# HomeAutomationModule.net
KiCad netlist of a schematic drawn in EAGLE
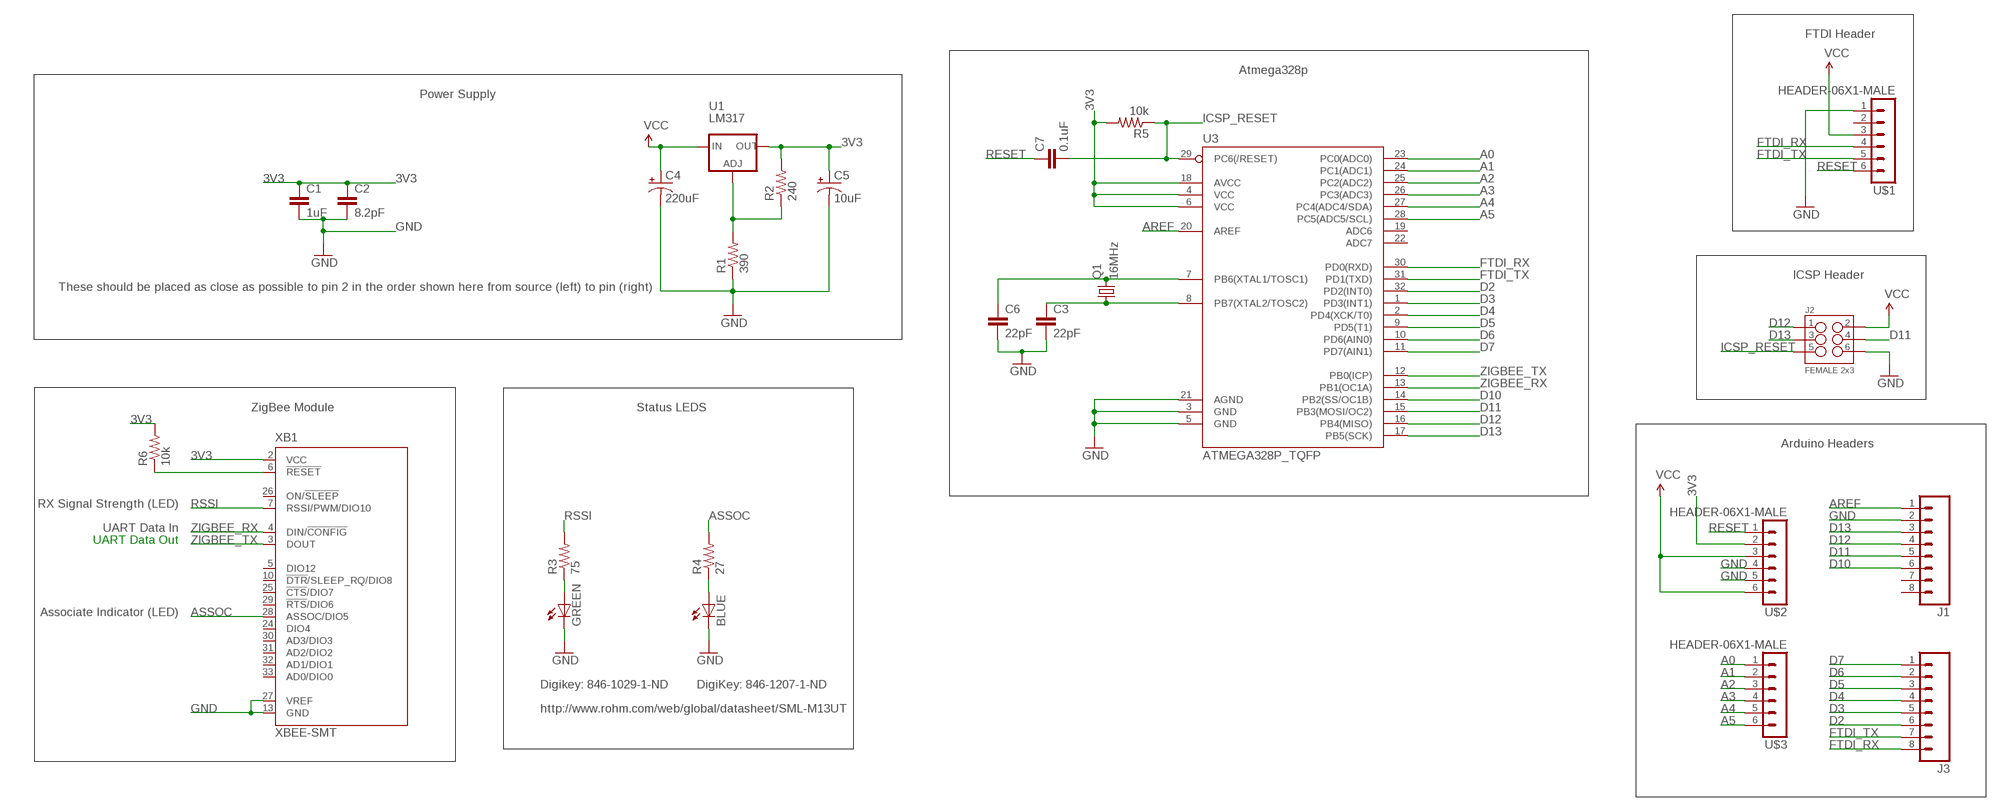
[diagram p0: schematic, sheet 1]

(export (version "E")
  (design (tool "Eeschema 10.0.6"))
  (components
    (comp (ref "BLUE")
      (value "LEDCHIP-LED0805")
      (footprint "eagle-import:CHIP-LED0805")
      (libsource (lib "eagle-import") (part "LEDCHIP-LED0805"))
    )
    (comp (ref "C1")
      (value "1uF")
      (footprint "eagle-import:0805-CAP")
      (libsource (lib "eagle-import") (part "1.0UF-25V-+80/-20(0805){dblquote}"))
    )
    (comp (ref "C2")
      (value "8.2pF")
      (footprint "eagle-import:0805-CAP")
      (libsource (lib "eagle-import") (part "1.0UF-25V-+80/-20(0805){dblquote}"))
    )
    (comp (ref "C3")
      (value "22pF")
      (footprint "eagle-import:0805-CAP")
      (libsource (lib "eagle-import") (part "2.2UF-25V-+80/-20(0805)"))
    )
    (comp (ref "C4")
      (value "220uF")
      (footprint "eagle-import:CPOL-RADIAL-10UF-25V")
      (libsource (lib "eagle-import") (part "CAP_POLPTH2"))
    )
    (comp (ref "C5")
      (value "10uF")
      (footprint "eagle-import:CPOL-RADIAL-10UF-25V")
      (libsource (lib "eagle-import") (part "CAP_POLPTH2"))
    )
    (comp (ref "C6")
      (value "22pF")
      (footprint "eagle-import:0805-CAP")
      (libsource (lib "eagle-import") (part "2.2UF-25V-+80/-20(0805)"))
    )
    (comp (ref "C7")
      (value "0.1uF")
      (footprint "eagle-import:0805-CAP")
      (libsource (lib "eagle-import") (part "2.2UF-25V-+80/-20(0805)"))
    )
    (comp (ref "GREEN")
      (value "LEDCHIP-LED0805")
      (footprint "eagle-import:CHIP-LED0805")
      (libsource (lib "eagle-import") (part "LEDCHIP-LED0805"))
    )
    (comp (ref "J1")
      (value "M08")
      (footprint "eagle-import:1X08_ROUND")
      (libsource (lib "eagle-import") (part "M08"))
    )
    (comp (ref "J2")
      (value "FEMALE 2x3")
      (footprint "eagle-import:2X3")
      (libsource (lib "eagle-import") (part "M03X2FEMALE"))
    )
    (comp (ref "J3")
      (value "M08")
      (footprint "eagle-import:1X08_ROUND")
      (libsource (lib "eagle-import") (part "M08"))
    )
    (comp (ref "Q1")
      (value "16MHz")
      (footprint "eagle-import:HC49_S")
      (libsource (lib "eagle-import") (part "CRYSTALHC49S"))
    )
    (comp (ref "R1")
      (value "390")
      (footprint "eagle-import:0805")
      (libsource (lib "eagle-import") (part "RESISTOR0805-RES"))
    )
    (comp (ref "R2")
      (value "240")
      (footprint "eagle-import:0805")
      (libsource (lib "eagle-import") (part "RESISTOR0805-RES"))
    )
    (comp (ref "R3")
      (value "75")
      (footprint "eagle-import:0805")
      (libsource (lib "eagle-import") (part "RESISTOR0805-RES"))
    )
    (comp (ref "R4")
      (value "27")
      (footprint "eagle-import:0805")
      (libsource (lib "eagle-import") (part "RESISTOR0805-RES"))
    )
    (comp (ref "R5")
      (value "10k")
      (footprint "eagle-import:0805")
      (libsource (lib "eagle-import") (part "RESISTOR0805-RES"))
    )
    (comp (ref "R6")
      (value "10k")
      (footprint "eagle-import:0805")
      (libsource (lib "eagle-import") (part "RESISTOR0805-RES"))
    )
    (comp (ref "U$1")
      (value "HEADER-06X1-MALE")
      (footprint "eagle-import:06X1-PTH")
      (libsource (lib "eagle-import") (part "HEADER-06X1?-MALE"))
    )
    (comp (ref "U$2")
      (value "HEADER-06X1-MALE")
      (footprint "eagle-import:06X1-PTH")
      (libsource (lib "eagle-import") (part "HEADER-06X1?-MALE"))
    )
    (comp (ref "U$3")
      (value "HEADER-06X1-MALE")
      (footprint "eagle-import:06X1-PTH")
      (libsource (lib "eagle-import") (part "HEADER-06X1?-MALE"))
    )
    (comp (ref "U1")
      (value "LM317")
      (footprint "eagle-import:SOT223")
      (libsource (lib "eagle-import") (part "V_REG_317SMD"))
    )
    (comp (ref "U3")
      (value "ATMEGA328P_TQFP")
      (footprint "eagle-import:TQFP32-08")
      (libsource (lib "eagle-import") (part "ATMEGA328P_TQFP"))
    )
    (comp (ref "XB1")
      (value "XBEE-SMT")
      (footprint "eagle-import:XBEE-SMT")
      (libsource (lib "eagle-import") (part "XBEE-SMT"))
    )
  )
  (nets
    (net (code "1") (name "/3V3") (class "Default")
      (node (ref "C1") (pin "1") (pinfunction "1_1") (pintype "passive"))
      (node (ref "C2") (pin "1") (pinfunction "1_1") (pintype "passive"))
      (node (ref "C5") (pin "1") (pinfunction "+_1") (pintype "passive"))
      (node (ref "R2") (pin "2") (pinfunction "2_2") (pintype "passive"))
      (node (ref "R5") (pin "2") (pinfunction "2_2") (pintype "passive"))
      (node (ref "R6") (pin "2") (pinfunction "2_2") (pintype "passive"))
      (node (ref "U$2") (pin "2") (pinfunction "2_2") (pintype "passive"))
      (node (ref "U1") (pin "2") (pinfunction "OUT_2") (pintype "output"))
      (node (ref "U3") (pin "18") (pinfunction "AVCC_18") (pintype "bidirectional"))
      (node (ref "U3") (pin "4") (pinfunction "VCC_4") (pintype "bidirectional"))
      (node (ref "U3") (pin "6") (pinfunction "VCC_6") (pintype "bidirectional"))
      (node (ref "XB1") (pin "2") (pinfunction "VCC_2") (pintype "power_in"))
    )
    (net (code "2") (name "/A0") (class "Default")
      (node (ref "U$3") (pin "1") (pinfunction "1_1") (pintype "passive"))
      (node (ref "U3") (pin "23") (pinfunction "PC0(ADC0)_23") (pintype "bidirectional"))
    )
    (net (code "3") (name "/A1") (class "Default")
      (node (ref "U$3") (pin "2") (pinfunction "2_2") (pintype "passive"))
      (node (ref "U3") (pin "24") (pinfunction "PC1(ADC1)_24") (pintype "bidirectional"))
    )
    (net (code "4") (name "/A2") (class "Default")
      (node (ref "U$3") (pin "3") (pinfunction "3_3") (pintype "passive"))
      (node (ref "U3") (pin "25") (pinfunction "PC2(ADC2)_25") (pintype "bidirectional"))
    )
    (net (code "5") (name "/A3") (class "Default")
      (node (ref "U$3") (pin "4") (pinfunction "4_4") (pintype "passive"))
      (node (ref "U3") (pin "26") (pinfunction "PC3(ADC3)_26") (pintype "bidirectional"))
    )
    (net (code "6") (name "/A4") (class "Default")
      (node (ref "U$3") (pin "5") (pinfunction "5_5") (pintype "passive"))
      (node (ref "U3") (pin "27") (pinfunction "PC4(ADC4/SDA)_27") (pintype "bidirectional"))
    )
    (net (code "7") (name "/A5") (class "Default")
      (node (ref "U$3") (pin "6") (pinfunction "6_6") (pintype "passive"))
      (node (ref "U3") (pin "28") (pinfunction "PC5(ADC5/SCL)_28") (pintype "bidirectional"))
    )
    (net (code "8") (name "/AREF") (class "Default")
      (node (ref "J1") (pin "1") (pinfunction "1_1") (pintype "passive"))
      (node (ref "U3") (pin "20") (pinfunction "AREF_20") (pintype "bidirectional"))
    )
    (net (code "9") (name "/ASSOC") (class "Default")
      (node (ref "R4") (pin "2") (pinfunction "2_2") (pintype "passive"))
      (node (ref "XB1") (pin "28") (pinfunction "ASSOC/DIO5_28") (pintype "bidirectional"))
    )
    (net (code "10") (name "/D2") (class "Default")
      (node (ref "J3") (pin "6") (pinfunction "6_6") (pintype "passive"))
      (node (ref "U3") (pin "32") (pinfunction "PD2(INT0)_32") (pintype "bidirectional"))
    )
    (net (code "11") (name "/D3") (class "Default")
      (node (ref "J3") (pin "5") (pinfunction "5_5") (pintype "passive"))
      (node (ref "U3") (pin "1") (pinfunction "PD3(INT1)_1") (pintype "bidirectional"))
    )
    (net (code "12") (name "/D4") (class "Default")
      (node (ref "J3") (pin "4") (pinfunction "4_4") (pintype "passive"))
      (node (ref "U3") (pin "2") (pinfunction "PD4(XCK/T0)_2") (pintype "bidirectional"))
    )
    (net (code "13") (name "/D5") (class "Default")
      (node (ref "J3") (pin "3") (pinfunction "3_3") (pintype "passive"))
      (node (ref "U3") (pin "9") (pinfunction "PD5(T1)_9") (pintype "bidirectional"))
    )
    (net (code "14") (name "/D6") (class "Default")
      (node (ref "J3") (pin "2") (pinfunction "2_2") (pintype "passive"))
      (node (ref "U3") (pin "10") (pinfunction "PD6(AIN0)_10") (pintype "bidirectional"))
    )
    (net (code "15") (name "/D7") (class "Default")
      (node (ref "J3") (pin "1") (pinfunction "1_1") (pintype "passive"))
      (node (ref "U3") (pin "11") (pinfunction "PD7(AIN1)_11") (pintype "bidirectional"))
    )
    (net (code "16") (name "/D10") (class "Default")
      (node (ref "J1") (pin "6") (pinfunction "6_6") (pintype "passive"))
      (node (ref "U3") (pin "14") (pinfunction "PB2(SS/OC1B)_14") (pintype "bidirectional"))
    )
    (net (code "17") (name "/D11") (class "Default")
      (node (ref "J1") (pin "5") (pinfunction "5_5") (pintype "passive"))
      (node (ref "J2") (pin "4") (pinfunction "4_4") (pintype "bidirectional"))
      (node (ref "U3") (pin "15") (pinfunction "PB3(MOSI/OC2)_15") (pintype "bidirectional"))
    )
    (net (code "18") (name "/D12") (class "Default")
      (node (ref "J1") (pin "4") (pinfunction "4_4") (pintype "passive"))
      (node (ref "J2") (pin "1") (pinfunction "1_1") (pintype "bidirectional"))
      (node (ref "U3") (pin "16") (pinfunction "PB4(MISO)_16") (pintype "bidirectional"))
    )
    (net (code "19") (name "/D13") (class "Default")
      (node (ref "J1") (pin "3") (pinfunction "3_3") (pintype "passive"))
      (node (ref "J2") (pin "3") (pinfunction "3_3") (pintype "bidirectional"))
      (node (ref "U3") (pin "17") (pinfunction "PB5(SCK)_17") (pintype "bidirectional"))
    )
    (net (code "20") (name "/FTDI_RX") (class "Default")
      (node (ref "J3") (pin "8") (pinfunction "8_8") (pintype "passive"))
      (node (ref "U$1") (pin "4") (pinfunction "4_4") (pintype "passive"))
      (node (ref "U3") (pin "30") (pinfunction "PD0(RXD)_30") (pintype "bidirectional"))
    )
    (net (code "21") (name "/FTDI_TX") (class "Default")
      (node (ref "J3") (pin "7") (pinfunction "7_7") (pintype "passive"))
      (node (ref "U$1") (pin "5") (pinfunction "5_5") (pintype "passive"))
      (node (ref "U3") (pin "31") (pinfunction "PD1(TXD)_31") (pintype "bidirectional"))
    )
    (net (code "22") (name "/ICSP_RESET") (class "Default")
      (node (ref "C7") (pin "2") (pinfunction "2_2") (pintype "passive"))
      (node (ref "J2") (pin "5") (pinfunction "5_5") (pintype "bidirectional"))
      (node (ref "R5") (pin "1") (pinfunction "1_1") (pintype "passive"))
      (node (ref "U3") (pin "29") (pinfunction "PC6(/RESET)_29") (pintype "bidirectional"))
    )
    (net (code "23") (name "/RESET") (class "Default")
      (node (ref "C7") (pin "1") (pinfunction "1_1") (pintype "passive"))
      (node (ref "U$1") (pin "6") (pinfunction "6_6") (pintype "passive"))
      (node (ref "U$2") (pin "1") (pinfunction "1_1") (pintype "passive"))
    )
    (net (code "24") (name "/RSSI") (class "Default")
      (node (ref "R3") (pin "2") (pinfunction "2_2") (pintype "passive"))
      (node (ref "XB1") (pin "7") (pinfunction "RSSI/PWM/DIO10_7") (pintype "output"))
    )
    (net (code "25") (name "/ZIGBEE_RX") (class "Default")
      (node (ref "U3") (pin "13") (pinfunction "PB1(OC1A)_13") (pintype "bidirectional"))
      (node (ref "XB1") (pin "4") (pinfunction "DIN/~{CONFIG}_4") (pintype "input"))
    )
    (net (code "26") (name "/ZIGBEE_TX") (class "Default")
      (node (ref "U3") (pin "12") (pinfunction "PB0(ICP)_12") (pintype "bidirectional"))
      (node (ref "XB1") (pin "3") (pinfunction "DOUT_3") (pintype "output"))
    )
    (net (code "27") (name "GND") (class "Default")
      (node (ref "BLUE") (pin "C") (pinfunction "C_C") (pintype "passive"))
      (node (ref "C1") (pin "2") (pinfunction "2_2") (pintype "passive"))
      (node (ref "C2") (pin "2") (pinfunction "2_2") (pintype "passive"))
      (node (ref "C3") (pin "2") (pinfunction "2_2") (pintype "passive"))
      (node (ref "C4") (pin "2") (pinfunction "-_2") (pintype "passive"))
      (node (ref "C5") (pin "2") (pinfunction "-_2") (pintype "passive"))
      (node (ref "C6") (pin "2") (pinfunction "2_2") (pintype "passive"))
      (node (ref "GREEN") (pin "C") (pinfunction "C_C") (pintype "passive"))
      (node (ref "J1") (pin "2") (pinfunction "2_2") (pintype "passive"))
      (node (ref "J2") (pin "6") (pinfunction "6_6") (pintype "bidirectional"))
      (node (ref "R1") (pin "1") (pinfunction "1_1") (pintype "passive"))
      (node (ref "U$1") (pin "1") (pinfunction "1_1") (pintype "passive"))
      (node (ref "U$2") (pin "4") (pinfunction "4_4") (pintype "passive"))
      (node (ref "U$2") (pin "5") (pinfunction "5_5") (pintype "passive"))
      (node (ref "U3") (pin "21") (pinfunction "AGND_21") (pintype "bidirectional"))
      (node (ref "U3") (pin "3") (pinfunction "GND_3") (pintype "bidirectional"))
      (node (ref "U3") (pin "5") (pinfunction "GND_5") (pintype "bidirectional"))
      (node (ref "XB1") (pin "13") (pinfunction "GND_13") (pintype "power_in"))
      (node (ref "XB1") (pin "27") (pinfunction "VREF_27") (pintype "input"))
    )
    (net (code "28") (name "Net-(BLUE-PadA)") (class "Default")
      (node (ref "BLUE") (pin "A") (pinfunction "A_A") (pintype "passive"))
      (node (ref "R4") (pin "1") (pinfunction "1_1") (pintype "passive"))
    )
    (net (code "29") (name "Net-(GREEN-PadA)") (class "Default")
      (node (ref "GREEN") (pin "A") (pinfunction "A_A") (pintype "passive"))
      (node (ref "R3") (pin "1") (pinfunction "1_1") (pintype "passive"))
    )
    (net (code "30") (name "Net-(U1-ADJ)") (class "Default")
      (node (ref "R1") (pin "2") (pinfunction "2_2") (pintype "passive"))
      (node (ref "R2") (pin "1") (pinfunction "1_1") (pintype "passive"))
      (node (ref "U1") (pin "1") (pinfunction "ADJ_1") (pintype "input"))
    )
    (net (code "31") (name "Net-(U3-PB6(XTAL1{slash}TOSC1))") (class "Default")
      (node (ref "C6") (pin "1") (pinfunction "1_1") (pintype "passive"))
      (node (ref "Q1") (pin "2") (pinfunction "2_2") (pintype "passive"))
      (node (ref "U3") (pin "7") (pinfunction "PB6(XTAL1/TOSC1)_7") (pintype "bidirectional"))
    )
    (net (code "32") (name "Net-(U3-PB7(XTAL2{slash}TOSC2))") (class "Default")
      (node (ref "C3") (pin "1") (pinfunction "1_1") (pintype "passive"))
      (node (ref "Q1") (pin "1") (pinfunction "1_1") (pintype "passive"))
      (node (ref "U3") (pin "8") (pinfunction "PB7(XTAL2/TOSC2)_8") (pintype "bidirectional"))
    )
    (net (code "33") (name "Net-(XB1-~{RESET})") (class "Default")
      (node (ref "R6") (pin "1") (pinfunction "1_1") (pintype "passive"))
      (node (ref "XB1") (pin "6") (pinfunction "~{RESET}_6") (pintype "input"))
    )
    (net (code "34") (name "VCC") (class "Default")
      (node (ref "C4") (pin "1") (pinfunction "+_1") (pintype "passive"))
      (node (ref "J2") (pin "2") (pinfunction "2_2") (pintype "bidirectional"))
      (node (ref "U$1") (pin "3") (pinfunction "3_3") (pintype "passive"))
      (node (ref "U$2") (pin "3") (pinfunction "3_3") (pintype "passive"))
      (node (ref "U$2") (pin "6") (pinfunction "6_6") (pintype "passive"))
      (node (ref "U1") (pin "3") (pinfunction "IN_3") (pintype "input"))
    )
    (net (code "35") (name "unconnected-(J1-Pad7)") (class "Default")
      (node (ref "J1") (pin "7") (pinfunction "7_7") (pintype "passive"))
    )
    (net (code "36") (name "unconnected-(J1-Pad8)") (class "Default")
      (node (ref "J1") (pin "8") (pinfunction "8_8") (pintype "passive"))
    )
    (net (code "37") (name "unconnected-(U$1-Pad2)") (class "Default")
      (node (ref "U$1") (pin "2") (pinfunction "2_2") (pintype "passive"))
    )
    (net (code "38") (name "unconnected-(U3-ADC6-Pad19)") (class "Default")
      (node (ref "U3") (pin "19") (pinfunction "ADC6_19") (pintype "bidirectional"))
    )
    (net (code "39") (name "unconnected-(U3-ADC7-Pad22)") (class "Default")
      (node (ref "U3") (pin "22") (pinfunction "ADC7_22") (pintype "bidirectional"))
    )
    (net (code "40") (name "unconnected-(XB1-AD0{slash}DIO0-Pad33)") (class "Default")
      (node (ref "XB1") (pin "33") (pinfunction "AD0/DIO0_33") (pintype "bidirectional"))
    )
    (net (code "41") (name "unconnected-(XB1-AD1{slash}DIO1-Pad32)") (class "Default")
      (node (ref "XB1") (pin "32") (pinfunction "AD1/DIO1_32") (pintype "bidirectional"))
    )
    (net (code "42") (name "unconnected-(XB1-AD2{slash}DIO2-Pad31)") (class "Default")
      (node (ref "XB1") (pin "31") (pinfunction "AD2/DIO2_31") (pintype "bidirectional"))
    )
    (net (code "43") (name "unconnected-(XB1-AD3{slash}DIO3-Pad30)") (class "Default")
      (node (ref "XB1") (pin "30") (pinfunction "AD3/DIO3_30") (pintype "bidirectional"))
    )
    (net (code "44") (name "unconnected-(XB1-DIO4-Pad24)") (class "Default")
      (node (ref "XB1") (pin "24") (pinfunction "DIO4_24") (pintype "bidirectional"))
    )
    (net (code "45") (name "unconnected-(XB1-DIO12-Pad5)") (class "Default")
      (node (ref "XB1") (pin "5") (pinfunction "DIO12_5") (pintype "bidirectional"))
    )
    (net (code "46") (name "unconnected-(XB1-ON{slash}~{SLEEP}-Pad26)") (class "Default")
      (node (ref "XB1") (pin "26") (pinfunction "ON/~{SLEEP}_26") (pintype "output"))
    )
    (net (code "47") (name "unconnected-(XB1-~{CTS}{slash}DIO7-Pad25)") (class "Default")
      (node (ref "XB1") (pin "25") (pinfunction "~{CTS}/DIO7_25") (pintype "bidirectional"))
    )
    (net (code "48") (name "unconnected-(XB1-~{DTR}{slash}SLEEP_RQ{slash}DIO8-Pad10)") (class "Default")
      (node (ref "XB1") (pin "10") (pinfunction "~{DTR}/SLEEP_RQ/DIO8_10") (pintype "bidirectional"))
    )
    (net (code "49") (name "unconnected-(XB1-~{RTS}{slash}DIO6-Pad29)") (class "Default")
      (node (ref "XB1") (pin "29") (pinfunction "~{RTS}/DIO6_29") (pintype "bidirectional"))
    )
  )
)
